# TSS_Rev3_Shield.net
KiCad netlist of a schematic drawn in EAGLE
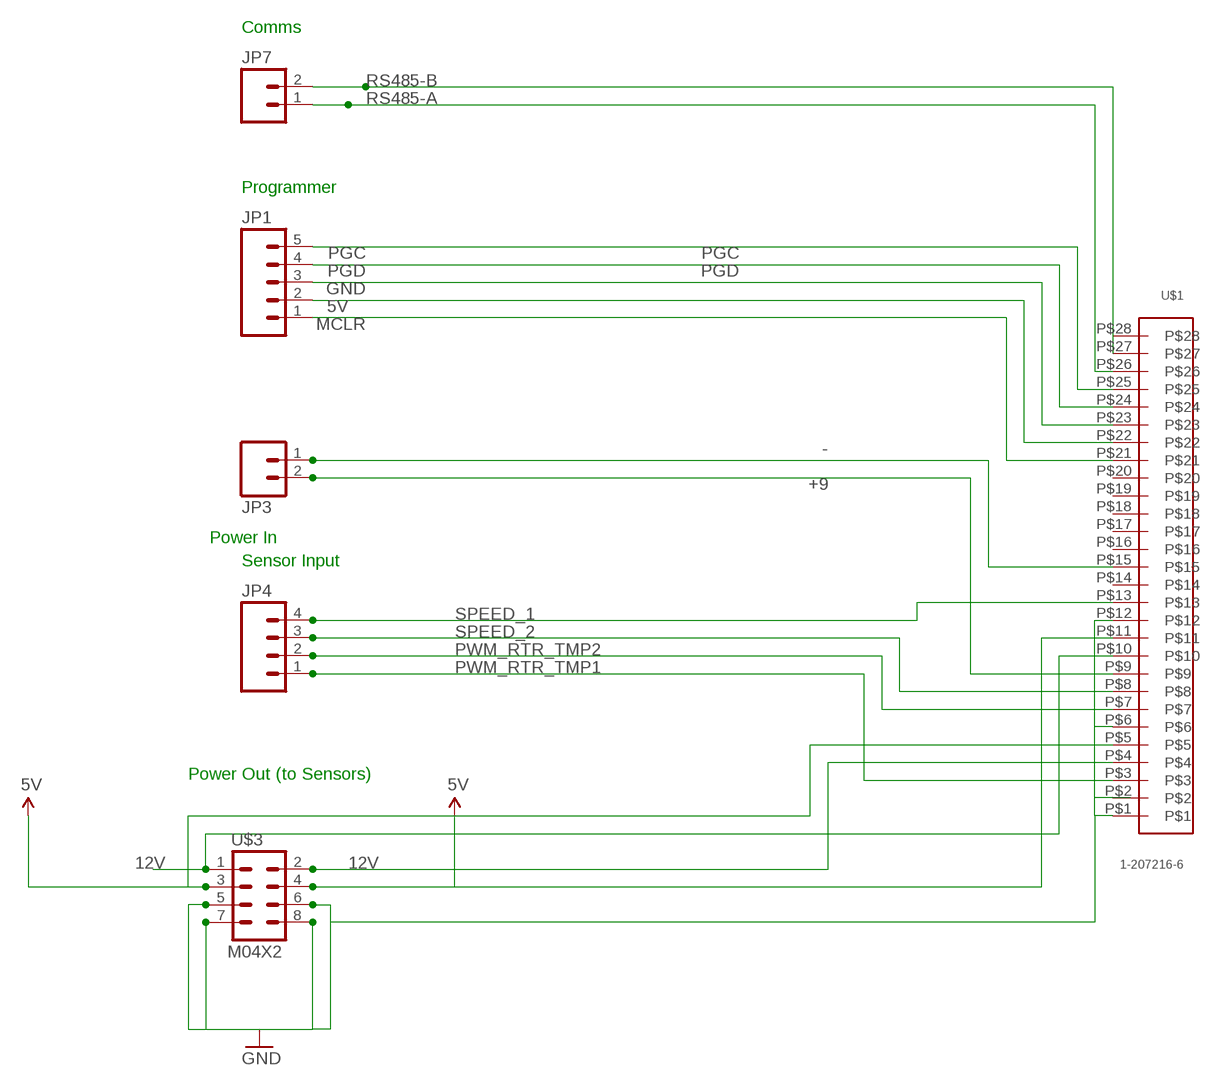
[diagram p0: schematic, sheet 1]

(export (version "E")
  (design (tool "Eeschema 10.0.6"))
  (components
    (comp (ref "JP1")
      (value "M05PTH")
      (footprint "eagle-import:1X05")
      (libsource (lib "eagle-import") (part "M05PTH"))
    )
    (comp (ref "JP3")
      (value "M02LOCK")
      (footprint "eagle-import:1X02_LOCK")
      (libsource (lib "eagle-import") (part "M02LOCK"))
    )
    (comp (ref "JP4")
      (value "M04PTH")
      (footprint "eagle-import:1X04")
      (libsource (lib "eagle-import") (part "M04PTH"))
    )
    (comp (ref "JP7")
      (value "M02PTH")
      (footprint "eagle-import:1X02")
      (libsource (lib "eagle-import") (part "M02PTH"))
    )
    (comp (ref "U$1")
      (value "1-207216-6")
      (footprint "eagle-import:1-207216-6")
      (libsource (lib "eagle-import") (part "1-207216-6"))
    )
    (comp (ref "U$3")
      (value "M04X2")
      (footprint "eagle-import:2X4")
      (libsource (lib "eagle-import") (part "M04X2"))
    )
  )
  (nets
    (net (code "1") (name "/+9") (class "Default")
      (node (ref "JP3") (pin "2") (pinfunction "2_2") (pintype "passive"))
      (node (ref "U$1") (pin "P$9") (pinfunction "P$9_P$9") (pintype "bidirectional"))
    )
    (net (code "2") (name "/-") (class "Default")
      (node (ref "JP3") (pin "1") (pinfunction "1_1") (pintype "passive"))
      (node (ref "U$1") (pin "P$15") (pinfunction "P$15_P$15") (pintype "bidirectional"))
    )
    (net (code "3") (name "/12V") (class "Default")
      (node (ref "U$1") (pin "P$10") (pinfunction "P$10_P$10") (pintype "bidirectional"))
      (node (ref "U$1") (pin "P$4") (pinfunction "P$4_P$4") (pintype "bidirectional"))
      (node (ref "U$3") (pin "1") (pinfunction "1_1") (pintype "passive"))
      (node (ref "U$3") (pin "2") (pinfunction "2_2") (pintype "passive"))
    )
    (net (code "4") (name "/MCLR") (class "Default")
      (node (ref "JP1") (pin "1") (pinfunction "1_1") (pintype "passive"))
      (node (ref "U$1") (pin "P$21") (pinfunction "P$21_P$21") (pintype "bidirectional"))
    )
    (net (code "5") (name "/PGC") (class "Default")
      (node (ref "JP1") (pin "5") (pinfunction "5_5") (pintype "passive"))
      (node (ref "U$1") (pin "P$25") (pinfunction "P$25_P$25") (pintype "bidirectional"))
    )
    (net (code "6") (name "/PGD") (class "Default")
      (node (ref "JP1") (pin "4") (pinfunction "4_4") (pintype "passive"))
      (node (ref "U$1") (pin "P$24") (pinfunction "P$24_P$24") (pintype "bidirectional"))
    )
    (net (code "7") (name "/PWM_RTR_TMP1") (class "Default")
      (node (ref "JP4") (pin "1") (pinfunction "1_1") (pintype "passive"))
      (node (ref "U$1") (pin "P$3") (pinfunction "P$3_P$3") (pintype "bidirectional"))
    )
    (net (code "8") (name "/PWM_RTR_TMP2") (class "Default")
      (node (ref "JP4") (pin "2") (pinfunction "2_2") (pintype "passive"))
      (node (ref "U$1") (pin "P$7") (pinfunction "P$7_P$7") (pintype "bidirectional"))
    )
    (net (code "9") (name "/RS485-A") (class "Default")
      (node (ref "JP7") (pin "1") (pinfunction "1_1") (pintype "passive"))
      (node (ref "U$1") (pin "P$26") (pinfunction "P$26_P$26") (pintype "bidirectional"))
    )
    (net (code "10") (name "/RS485-B") (class "Default")
      (node (ref "JP7") (pin "2") (pinfunction "2_2") (pintype "passive"))
      (node (ref "U$1") (pin "P$27") (pinfunction "P$27_P$27") (pintype "bidirectional"))
    )
    (net (code "11") (name "/SPEED_1") (class "Default")
      (node (ref "JP4") (pin "4") (pinfunction "4_4") (pintype "passive"))
      (node (ref "U$1") (pin "P$13") (pinfunction "P$13_P$13") (pintype "bidirectional"))
    )
    (net (code "12") (name "/SPEED_2") (class "Default")
      (node (ref "JP4") (pin "3") (pinfunction "3_3") (pintype "passive"))
      (node (ref "U$1") (pin "P$8") (pinfunction "P$8_P$8") (pintype "bidirectional"))
    )
    (net (code "13") (name "5V") (class "Default")
      (node (ref "JP1") (pin "2") (pinfunction "2_2") (pintype "passive"))
      (node (ref "U$1") (pin "P$11") (pinfunction "P$11_P$11") (pintype "bidirectional"))
      (node (ref "U$1") (pin "P$22") (pinfunction "P$22_P$22") (pintype "bidirectional"))
      (node (ref "U$1") (pin "P$5") (pinfunction "P$5_P$5") (pintype "bidirectional"))
      (node (ref "U$3") (pin "3") (pinfunction "3_3") (pintype "passive"))
      (node (ref "U$3") (pin "4") (pinfunction "4_4") (pintype "passive"))
    )
    (net (code "14") (name "GND") (class "Default")
      (node (ref "JP1") (pin "3") (pinfunction "3_3") (pintype "passive"))
      (node (ref "U$1") (pin "P$1") (pinfunction "P$1_P$1") (pintype "bidirectional"))
      (node (ref "U$1") (pin "P$12") (pinfunction "P$12_P$12") (pintype "bidirectional"))
      (node (ref "U$1") (pin "P$23") (pinfunction "P$23_P$23") (pintype "bidirectional"))
      (node (ref "U$1") (pin "P$6") (pinfunction "P$6_P$6") (pintype "bidirectional"))
      (node (ref "U$3") (pin "5") (pinfunction "5_5") (pintype "passive"))
      (node (ref "U$3") (pin "6") (pinfunction "6_6") (pintype "passive"))
      (node (ref "U$3") (pin "7") (pinfunction "7_7") (pintype "passive"))
      (node (ref "U$3") (pin "8") (pinfunction "8_8") (pintype "passive"))
    )
    (net (code "15") (name "unconnected-(U$1-PadP$2)") (class "Default")
      (node (ref "U$1") (pin "P$2") (pinfunction "P$2_P$2") (pintype "bidirectional"))
    )
    (net (code "16") (name "unconnected-(U$1-PadP$14)") (class "Default")
      (node (ref "U$1") (pin "P$14") (pinfunction "P$14_P$14") (pintype "bidirectional"))
    )
    (net (code "17") (name "unconnected-(U$1-PadP$16)") (class "Default")
      (node (ref "U$1") (pin "P$16") (pinfunction "P$16_P$16") (pintype "bidirectional"))
    )
    (net (code "18") (name "unconnected-(U$1-PadP$17)") (class "Default")
      (node (ref "U$1") (pin "P$17") (pinfunction "P$17_P$17") (pintype "bidirectional"))
    )
    (net (code "19") (name "unconnected-(U$1-PadP$18)") (class "Default")
      (node (ref "U$1") (pin "P$18") (pinfunction "P$18_P$18") (pintype "bidirectional"))
    )
    (net (code "20") (name "unconnected-(U$1-PadP$19)") (class "Default")
      (node (ref "U$1") (pin "P$19") (pinfunction "P$19_P$19") (pintype "bidirectional"))
    )
    (net (code "21") (name "unconnected-(U$1-PadP$20)") (class "Default")
      (node (ref "U$1") (pin "P$20") (pinfunction "P$20_P$20") (pintype "bidirectional"))
    )
    (net (code "22") (name "unconnected-(U$1-PadP$28)") (class "Default")
      (node (ref "U$1") (pin "P$28") (pinfunction "P$28_P$28") (pintype "bidirectional"))
    )
  )
)
